# SuperCap.net
KiCad netlist of a schematic drawn in Altium Designer
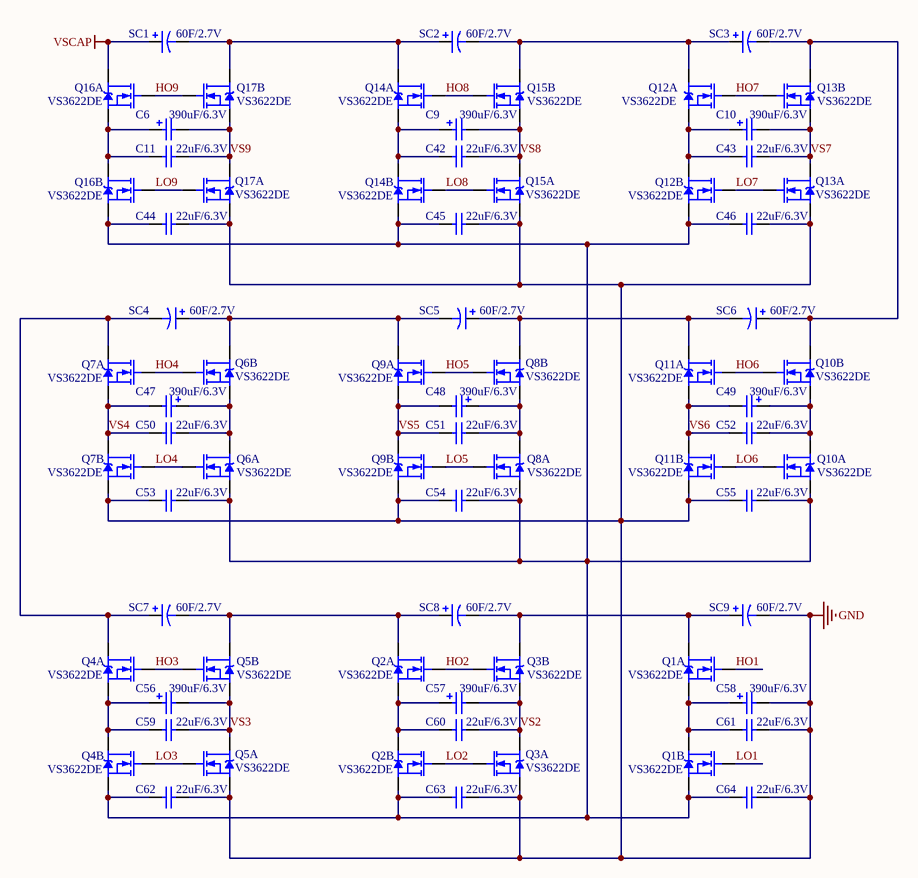
[diagram p0: SuperCap.SchDoc]

(export (version "E")
  (design (tool "Eeschema 10.0.6"))
  (components
    (comp (ref "C6")
      (value "390uF/6.3V")
      (footprint "CS 8*12 - B")
      (description "Polarized Capacitor (Axial)")
      (fields (field (name "PUBLISHER") "Altium Limited"))
      (libsource (lib "Miscellaneous Devices") (part "Cap Pol2"))
    )
    (comp (ref "C9")
      (value "390uF/6.3V")
      (footprint "CS 8*12 - B")
      (description "Polarized Capacitor (Axial)")
      (fields (field (name "PUBLISHER") "Altium Limited"))
      (libsource (lib "Miscellaneous Devices") (part "Cap Pol2"))
    )
    (comp (ref "C10")
      (value "390uF/6.3V")
      (footprint "CS 8*12 - B")
      (description "Polarized Capacitor (Axial)")
      (fields (field (name "PUBLISHER") "Altium Limited"))
      (libsource (lib "Miscellaneous Devices") (part "Cap Pol2"))
    )
    (comp (ref "C11")
      (value "22uF/6.3V")
      (footprint "C0603_M")
      (description "Capacitor")
      (fields (field (name "PUBLISHER") "Altium Limited"))
      (libsource (lib "Miscellaneous Devices") (part "Cap"))
    )
    (comp (ref "C42")
      (value "22uF/6.3V")
      (footprint "C0603_M")
      (description "Capacitor")
      (fields (field (name "PUBLISHER") "Altium Limited"))
      (libsource (lib "Miscellaneous Devices") (part "Cap"))
    )
    (comp (ref "C43")
      (value "22uF/6.3V")
      (footprint "C0603_M")
      (description "Capacitor")
      (fields (field (name "PUBLISHER") "Altium Limited"))
      (libsource (lib "Miscellaneous Devices") (part "Cap"))
    )
    (comp (ref "C44")
      (value "22uF/6.3V")
      (footprint "C0603_M")
      (description "Capacitor")
      (fields (field (name "PUBLISHER") "Altium Limited"))
      (libsource (lib "Miscellaneous Devices") (part "Cap"))
    )
    (comp (ref "C45")
      (value "22uF/6.3V")
      (footprint "C0603_M")
      (description "Capacitor")
      (fields (field (name "PUBLISHER") "Altium Limited"))
      (libsource (lib "Miscellaneous Devices") (part "Cap"))
    )
    (comp (ref "C46")
      (value "22uF/6.3V")
      (footprint "C0603_M")
      (description "Capacitor")
      (fields (field (name "PUBLISHER") "Altium Limited"))
      (libsource (lib "Miscellaneous Devices") (part "Cap"))
    )
    (comp (ref "C47")
      (value "390uF/6.3V")
      (footprint "CS 8*12 - B")
      (description "Polarized Capacitor (Axial)")
      (fields (field (name "PUBLISHER") "Altium Limited"))
      (libsource (lib "Miscellaneous Devices") (part "Cap Pol2"))
    )
    (comp (ref "C48")
      (value "390uF/6.3V")
      (footprint "CS 8*12 - B")
      (description "Polarized Capacitor (Axial)")
      (fields (field (name "PUBLISHER") "Altium Limited"))
      (libsource (lib "Miscellaneous Devices") (part "Cap Pol2"))
    )
    (comp (ref "C49")
      (value "390uF/6.3V")
      (footprint "CS 8*12 - B")
      (description "Polarized Capacitor (Axial)")
      (fields (field (name "PUBLISHER") "Altium Limited"))
      (libsource (lib "Miscellaneous Devices") (part "Cap Pol2"))
    )
    (comp (ref "C50")
      (value "22uF/6.3V")
      (footprint "C0603_M")
      (description "Capacitor")
      (fields (field (name "PUBLISHER") "Altium Limited"))
      (libsource (lib "Miscellaneous Devices") (part "Cap"))
    )
    (comp (ref "C51")
      (value "22uF/6.3V")
      (footprint "C0603_M")
      (description "Capacitor")
      (fields (field (name "PUBLISHER") "Altium Limited"))
      (libsource (lib "Miscellaneous Devices") (part "Cap"))
    )
    (comp (ref "C52")
      (value "22uF/6.3V")
      (footprint "C0603_M")
      (description "Capacitor")
      (fields (field (name "PUBLISHER") "Altium Limited"))
      (libsource (lib "Miscellaneous Devices") (part "Cap"))
    )
    (comp (ref "C53")
      (value "22uF/6.3V")
      (footprint "C0603_M")
      (description "Capacitor")
      (fields (field (name "PUBLISHER") "Altium Limited"))
      (libsource (lib "Miscellaneous Devices") (part "Cap"))
    )
    (comp (ref "C54")
      (value "22uF/6.3V")
      (footprint "C0603_M")
      (description "Capacitor")
      (fields (field (name "PUBLISHER") "Altium Limited"))
      (libsource (lib "Miscellaneous Devices") (part "Cap"))
    )
    (comp (ref "C55")
      (value "22uF/6.3V")
      (footprint "C0603_M")
      (description "Capacitor")
      (fields (field (name "PUBLISHER") "Altium Limited"))
      (libsource (lib "Miscellaneous Devices") (part "Cap"))
    )
    (comp (ref "C56")
      (value "390uF/6.3V")
      (footprint "CS 8*12 - B")
      (description "Polarized Capacitor (Axial)")
      (fields (field (name "PUBLISHER") "Altium Limited"))
      (libsource (lib "Miscellaneous Devices") (part "Cap Pol2"))
    )
    (comp (ref "C57")
      (value "390uF/6.3V")
      (footprint "CS 8*12 - B")
      (description "Polarized Capacitor (Axial)")
      (fields (field (name "PUBLISHER") "Altium Limited"))
      (libsource (lib "Miscellaneous Devices") (part "Cap Pol2"))
    )
    (comp (ref "C58")
      (value "390uF/6.3V")
      (footprint "CS 8*12 - B")
      (description "Polarized Capacitor (Axial)")
      (fields (field (name "PUBLISHER") "Altium Limited"))
      (libsource (lib "Miscellaneous Devices") (part "Cap Pol2"))
    )
    (comp (ref "C59")
      (value "22uF/6.3V")
      (footprint "C0603_M")
      (description "Capacitor")
      (fields (field (name "PUBLISHER") "Altium Limited"))
      (libsource (lib "Miscellaneous Devices") (part "Cap"))
    )
    (comp (ref "C60")
      (value "22uF/6.3V")
      (footprint "C0603_M")
      (description "Capacitor")
      (fields (field (name "PUBLISHER") "Altium Limited"))
      (libsource (lib "Miscellaneous Devices") (part "Cap"))
    )
    (comp (ref "C61")
      (value "22uF/6.3V")
      (footprint "C0603_M")
      (description "Capacitor")
      (fields (field (name "PUBLISHER") "Altium Limited"))
      (libsource (lib "Miscellaneous Devices") (part "Cap"))
    )
    (comp (ref "C62")
      (value "22uF/6.3V")
      (footprint "C0603_M")
      (description "Capacitor")
      (fields (field (name "PUBLISHER") "Altium Limited"))
      (libsource (lib "Miscellaneous Devices") (part "Cap"))
    )
    (comp (ref "C63")
      (value "22uF/6.3V")
      (footprint "C0603_M")
      (description "Capacitor")
      (fields (field (name "PUBLISHER") "Altium Limited"))
      (libsource (lib "Miscellaneous Devices") (part "Cap"))
    )
    (comp (ref "C64")
      (value "22uF/6.3V")
      (footprint "C0603_M")
      (description "Capacitor")
      (libsource (lib "Miscellaneous Devices") (part "Cap"))
    )
    (comp (ref "Q1")
      (value "VS3622DE")
      (footprint "PDFN3333-8_VS3622DE")
      (libsource (lib "my_library") (part "VS3622DE"))
    )
    (comp (ref "Q2")
      (value "VS3622DE")
      (footprint "PDFN3333-8_VS3622DE")
      (libsource (lib "my_library") (part "VS3622DE"))
    )
    (comp (ref "Q3")
      (value "VS3622DE")
      (footprint "PDFN3333-8_VS3622DE")
      (libsource (lib "my_library") (part "VS3622DE"))
    )
    (comp (ref "Q4")
      (value "VS3622DE")
      (footprint "PDFN3333-8_VS3622DE")
      (libsource (lib "my_library") (part "VS3622DE"))
    )
    (comp (ref "Q5")
      (value "VS3622DE")
      (footprint "PDFN3333-8_VS3622DE")
      (libsource (lib "my_library") (part "VS3622DE"))
    )
    (comp (ref "Q6")
      (value "VS3622DE")
      (footprint "PDFN3333-8_VS3622DE")
      (libsource (lib "my_library") (part "VS3622DE"))
    )
    (comp (ref "Q7")
      (value "VS3622DE")
      (footprint "PDFN3333-8_VS3622DE")
      (libsource (lib "my_library") (part "VS3622DE"))
    )
    (comp (ref "Q8")
      (value "VS3622DE")
      (footprint "PDFN3333-8_VS3622DE")
      (libsource (lib "my_library") (part "VS3622DE"))
    )
    (comp (ref "Q9")
      (value "VS3622DE")
      (footprint "PDFN3333-8_VS3622DE")
      (libsource (lib "my_library") (part "VS3622DE"))
    )
    (comp (ref "Q10")
      (value "VS3622DE")
      (footprint "PDFN3333-8_VS3622DE")
      (libsource (lib "my_library") (part "VS3622DE"))
    )
    (comp (ref "Q11")
      (value "VS3622DE")
      (footprint "PDFN3333-8_VS3622DE")
      (libsource (lib "my_library") (part "VS3622DE"))
    )
    (comp (ref "Q12")
      (value "VS3622DE")
      (footprint "PDFN3333-8_VS3622DE")
      (libsource (lib "my_library") (part "VS3622DE"))
    )
    (comp (ref "Q13")
      (value "VS3622DE")
      (footprint "PDFN3333-8_VS3622DE")
      (libsource (lib "my_library") (part "VS3622DE"))
    )
    (comp (ref "Q14")
      (value "VS3622DE")
      (footprint "PDFN3333-8_VS3622DE")
      (libsource (lib "my_library") (part "VS3622DE"))
    )
    (comp (ref "Q15")
      (value "VS3622DE")
      (footprint "PDFN3333-8_VS3622DE")
      (libsource (lib "my_library") (part "VS3622DE"))
    )
    (comp (ref "Q16")
      (value "VS3622DE")
      (footprint "PDFN3333-8_VS3622DE")
      (libsource (lib "my_library") (part "VS3622DE"))
    )
    (comp (ref "Q17")
      (value "VS3622DE")
      (footprint "PDFN3333-8_VS3622DE")
      (libsource (lib "my_library") (part "VS3622DE"))
    )
    (comp (ref "SC1")
      (value "60F/2.7V")
      (footprint "CE-7.5*18*35.5 - BK")
      (description "Polarized Capacitor (Radial)")
      (libsource (lib "Miscellaneous Devices") (part "Cap Pol1"))
    )
    (comp (ref "SC2")
      (value "60F/2.7V")
      (footprint "CE-7.5*18*35.5 - BK")
      (description "Polarized Capacitor (Radial)")
      (libsource (lib "Miscellaneous Devices") (part "Cap Pol1"))
    )
    (comp (ref "SC3")
      (value "60F/2.7V")
      (footprint "CE-7.5*18*35.5 - BK")
      (description "Polarized Capacitor (Radial)")
      (libsource (lib "Miscellaneous Devices") (part "Cap Pol1"))
    )
    (comp (ref "SC4")
      (value "60F/2.7V")
      (footprint "CE-7.5*18*35.5 - BK")
      (description "Polarized Capacitor (Radial)")
      (libsource (lib "") (part "Cap Pol1_1"))
    )
    (comp (ref "SC5")
      (value "60F/2.7V")
      (footprint "CE-7.5*18*35.5 - BK")
      (description "Polarized Capacitor (Radial)")
      (libsource (lib "") (part "Cap Pol1_1"))
    )
    (comp (ref "SC6")
      (value "60F/2.7V")
      (footprint "CE-7.5*18*35.5 - BK")
      (description "Polarized Capacitor (Radial)")
      (libsource (lib "") (part "Cap Pol1_1"))
    )
    (comp (ref "SC7")
      (value "60F/2.7V")
      (footprint "CE-7.5*18*35.5 - BK")
      (description "Polarized Capacitor (Radial)")
      (libsource (lib "Miscellaneous Devices") (part "Cap Pol1"))
    )
    (comp (ref "SC8")
      (value "60F/2.7V")
      (footprint "CE-7.5*18*35.5 - BK")
      (description "Polarized Capacitor (Radial)")
      (libsource (lib "Miscellaneous Devices") (part "Cap Pol1"))
    )
    (comp (ref "SC9")
      (value "60F/2.7V")
      (footprint "CE-7.5*18*35.5 - BK")
      (description "Polarized Capacitor (Radial)")
      (libsource (lib "Miscellaneous Devices") (part "Cap Pol1"))
    )
  )
  (nets
    (net (code "1") (name "/HO1") (class "Default")
      (node (ref "Q1") (pin "G1") (pinfunction "G1_G1") (pintype "passive"))
    )
    (net (code "2") (name "/HO2") (class "Default")
      (node (ref "Q2") (pin "G1") (pinfunction "G1_G1") (pintype "passive"))
      (node (ref "Q3") (pin "G2") (pinfunction "G2_G2") (pintype "passive"))
    )
    (net (code "3") (name "/HO3") (class "Default")
      (node (ref "Q4") (pin "G1") (pinfunction "G1_G1") (pintype "passive"))
      (node (ref "Q5") (pin "G2") (pinfunction "G2_G2") (pintype "passive"))
    )
    (net (code "4") (name "/HO4") (class "Default")
      (node (ref "Q6") (pin "G2") (pinfunction "G2_G2") (pintype "passive"))
      (node (ref "Q7") (pin "G1") (pinfunction "G1_G1") (pintype "passive"))
    )
    (net (code "5") (name "/HO5") (class "Default")
      (node (ref "Q8") (pin "G2") (pinfunction "G2_G2") (pintype "passive"))
      (node (ref "Q9") (pin "G1") (pinfunction "G1_G1") (pintype "passive"))
    )
    (net (code "6") (name "/HO6") (class "Default")
      (node (ref "Q10") (pin "G2") (pinfunction "G2_G2") (pintype "passive"))
      (node (ref "Q11") (pin "G1") (pinfunction "G1_G1") (pintype "passive"))
    )
    (net (code "7") (name "/HO7") (class "Default")
      (node (ref "Q12") (pin "G1") (pinfunction "G1_G1") (pintype "passive"))
      (node (ref "Q13") (pin "G2") (pinfunction "G2_G2") (pintype "passive"))
    )
    (net (code "8") (name "/HO8") (class "Default")
      (node (ref "Q14") (pin "G1") (pinfunction "G1_G1") (pintype "passive"))
      (node (ref "Q15") (pin "G2") (pinfunction "G2_G2") (pintype "passive"))
    )
    (net (code "9") (name "/HO9") (class "Default")
      (node (ref "Q16") (pin "G1") (pinfunction "G1_G1") (pintype "passive"))
      (node (ref "Q17") (pin "G2") (pinfunction "G2_G2") (pintype "passive"))
    )
    (net (code "10") (name "/LO1") (class "Default")
      (node (ref "Q1") (pin "G2") (pinfunction "G2_G2") (pintype "passive"))
    )
    (net (code "11") (name "/LO2") (class "Default")
      (node (ref "Q2") (pin "G2") (pinfunction "G2_G2") (pintype "passive"))
      (node (ref "Q3") (pin "G1") (pinfunction "G1_G1") (pintype "passive"))
    )
    (net (code "12") (name "/LO3") (class "Default")
      (node (ref "Q4") (pin "G2") (pinfunction "G2_G2") (pintype "passive"))
      (node (ref "Q5") (pin "G1") (pinfunction "G1_G1") (pintype "passive"))
    )
    (net (code "13") (name "/LO4") (class "Default")
      (node (ref "Q6") (pin "G1") (pinfunction "G1_G1") (pintype "passive"))
      (node (ref "Q7") (pin "G2") (pinfunction "G2_G2") (pintype "passive"))
    )
    (net (code "14") (name "/LO5") (class "Default")
      (node (ref "Q8") (pin "G1") (pinfunction "G1_G1") (pintype "passive"))
      (node (ref "Q9") (pin "G2") (pinfunction "G2_G2") (pintype "passive"))
    )
    (net (code "15") (name "/LO6") (class "Default")
      (node (ref "Q10") (pin "G1") (pinfunction "G1_G1") (pintype "passive"))
      (node (ref "Q11") (pin "G2") (pinfunction "G2_G2") (pintype "passive"))
    )
    (net (code "16") (name "/LO7") (class "Default")
      (node (ref "Q12") (pin "G2") (pinfunction "G2_G2") (pintype "passive"))
      (node (ref "Q13") (pin "G1") (pinfunction "G1_G1") (pintype "passive"))
    )
    (net (code "17") (name "/LO8") (class "Default")
      (node (ref "Q14") (pin "G2") (pinfunction "G2_G2") (pintype "passive"))
      (node (ref "Q15") (pin "G1") (pinfunction "G1_G1") (pintype "passive"))
    )
    (net (code "18") (name "/LO9") (class "Default")
      (node (ref "Q16") (pin "G2") (pinfunction "G2_G2") (pintype "passive"))
      (node (ref "Q17") (pin "G1") (pinfunction "G1_G1") (pintype "passive"))
    )
    (net (code "19") (name "/VS2") (class "Default")
      (node (ref "C57") (pin "2") (pinfunction "2_2") (pintype "passive"))
      (node (ref "C60") (pin "2") (pinfunction "2_2") (pintype "passive"))
      (node (ref "Q3") (pin "D1") (pinfunction "D1_D1") (pintype "passive"))
      (node (ref "Q3") (pin "S2") (pinfunction "S2_S2") (pintype "passive"))
    )
    (net (code "20") (name "/VS3") (class "Default")
      (node (ref "C56") (pin "2") (pinfunction "2_2") (pintype "passive"))
      (node (ref "C59") (pin "2") (pinfunction "2_2") (pintype "passive"))
      (node (ref "Q5") (pin "D1") (pinfunction "D1_D1") (pintype "passive"))
      (node (ref "Q5") (pin "S2") (pinfunction "S2_S2") (pintype "passive"))
    )
    (net (code "21") (name "/VS4") (class "Default")
      (node (ref "C47") (pin "2") (pinfunction "2_2") (pintype "passive"))
      (node (ref "C50") (pin "1") (pinfunction "1_1") (pintype "passive"))
      (node (ref "Q7") (pin "D2") (pinfunction "D2_D2") (pintype "passive"))
      (node (ref "Q7") (pin "S1") (pinfunction "S1_S1") (pintype "passive"))
    )
    (net (code "22") (name "/VS5") (class "Default")
      (node (ref "C48") (pin "2") (pinfunction "2_2") (pintype "passive"))
      (node (ref "C51") (pin "1") (pinfunction "1_1") (pintype "passive"))
      (node (ref "Q9") (pin "D2") (pinfunction "D2_D2") (pintype "passive"))
      (node (ref "Q9") (pin "S1") (pinfunction "S1_S1") (pintype "passive"))
    )
    (net (code "23") (name "/VS6") (class "Default")
      (node (ref "C49") (pin "2") (pinfunction "2_2") (pintype "passive"))
      (node (ref "C52") (pin "1") (pinfunction "1_1") (pintype "passive"))
      (node (ref "Q11") (pin "D2") (pinfunction "D2_D2") (pintype "passive"))
      (node (ref "Q11") (pin "S1") (pinfunction "S1_S1") (pintype "passive"))
    )
    (net (code "24") (name "/VS7") (class "Default")
      (node (ref "C10") (pin "2") (pinfunction "2_2") (pintype "passive"))
      (node (ref "C43") (pin "2") (pinfunction "2_2") (pintype "passive"))
      (node (ref "Q13") (pin "D1") (pinfunction "D1_D1") (pintype "passive"))
      (node (ref "Q13") (pin "S2") (pinfunction "S2_S2") (pintype "passive"))
    )
    (net (code "25") (name "/VS8") (class "Default")
      (node (ref "C42") (pin "2") (pinfunction "2_2") (pintype "passive"))
      (node (ref "C9") (pin "2") (pinfunction "2_2") (pintype "passive"))
      (node (ref "Q15") (pin "D1") (pinfunction "D1_D1") (pintype "passive"))
      (node (ref "Q15") (pin "S2") (pinfunction "S2_S2") (pintype "passive"))
    )
    (net (code "26") (name "/VS9") (class "Default")
      (node (ref "C11") (pin "2") (pinfunction "2_2") (pintype "passive"))
      (node (ref "C6") (pin "2") (pinfunction "2_2") (pintype "passive"))
      (node (ref "Q17") (pin "D1") (pinfunction "D1_D1") (pintype "passive"))
      (node (ref "Q17") (pin "S2") (pinfunction "S2_S2") (pintype "passive"))
    )
    (net (code "27") (name "GND") (class "Default")
      (node (ref "C44") (pin "2") (pinfunction "2_2") (pintype "passive"))
      (node (ref "C45") (pin "2") (pinfunction "2_2") (pintype "passive"))
      (node (ref "C46") (pin "2") (pinfunction "2_2") (pintype "passive"))
      (node (ref "C53") (pin "1") (pinfunction "1_1") (pintype "passive"))
      (node (ref "C54") (pin "1") (pinfunction "1_1") (pintype "passive"))
      (node (ref "C55") (pin "1") (pinfunction "1_1") (pintype "passive"))
      (node (ref "C58") (pin "2") (pinfunction "2_2") (pintype "passive"))
      (node (ref "C61") (pin "2") (pinfunction "2_2") (pintype "passive"))
      (node (ref "C62") (pin "2") (pinfunction "2_2") (pintype "passive"))
      (node (ref "C63") (pin "2") (pinfunction "2_2") (pintype "passive"))
      (node (ref "C64") (pin "1") (pinfunction "1_1") (pintype "passive"))
      (node (ref "Q11") (pin "S2") (pinfunction "S2_S2") (pintype "passive"))
      (node (ref "Q13") (pin "S1") (pinfunction "S1_S1") (pintype "passive"))
      (node (ref "Q15") (pin "S1") (pinfunction "S1_S1") (pintype "passive"))
      (node (ref "Q17") (pin "S1") (pinfunction "S1_S1") (pintype "passive"))
      (node (ref "Q3") (pin "S1") (pinfunction "S1_S1") (pintype "passive"))
      (node (ref "Q5") (pin "S1") (pinfunction "S1_S1") (pintype "passive"))
      (node (ref "Q7") (pin "S2") (pinfunction "S2_S2") (pintype "passive"))
      (node (ref "Q9") (pin "S2") (pinfunction "S2_S2") (pintype "passive"))
      (node (ref "SC9") (pin "2") (pinfunction "2_2") (pintype "passive"))
    )
    (net (code "28") (name "Net-(C10-Pad1)") (class "Default")
      (node (ref "C10") (pin "1") (pinfunction "1_1") (pintype "passive"))
      (node (ref "C43") (pin "1") (pinfunction "1_1") (pintype "passive"))
      (node (ref "Q12") (pin "D2") (pinfunction "D2_D2") (pintype "passive"))
      (node (ref "Q12") (pin "S1") (pinfunction "S1_S1") (pintype "passive"))
    )
    (net (code "29") (name "Net-(C11-Pad1)") (class "Default")
      (node (ref "C11") (pin "1") (pinfunction "1_1") (pintype "passive"))
      (node (ref "C6") (pin "1") (pinfunction "1_1") (pintype "passive"))
      (node (ref "Q16") (pin "D2") (pinfunction "D2_D2") (pintype "passive"))
      (node (ref "Q16") (pin "S1") (pinfunction "S1_S1") (pintype "passive"))
    )
    (net (code "30") (name "Net-(C42-Pad1)") (class "Default")
      (node (ref "C42") (pin "1") (pinfunction "1_1") (pintype "passive"))
      (node (ref "C9") (pin "1") (pinfunction "1_1") (pintype "passive"))
      (node (ref "Q14") (pin "D2") (pinfunction "D2_D2") (pintype "passive"))
      (node (ref "Q14") (pin "S1") (pinfunction "S1_S1") (pintype "passive"))
    )
    (net (code "31") (name "Net-(C44-Pad1)") (class "Default")
      (node (ref "C44") (pin "1") (pinfunction "1_1") (pintype "passive"))
      (node (ref "C45") (pin "1") (pinfunction "1_1") (pintype "passive"))
      (node (ref "C46") (pin "1") (pinfunction "1_1") (pintype "passive"))
      (node (ref "C53") (pin "2") (pinfunction "2_2") (pintype "passive"))
      (node (ref "C54") (pin "2") (pinfunction "2_2") (pintype "passive"))
      (node (ref "C55") (pin "2") (pinfunction "2_2") (pintype "passive"))
      (node (ref "C62") (pin "1") (pinfunction "1_1") (pintype "passive"))
      (node (ref "C63") (pin "1") (pinfunction "1_1") (pintype "passive"))
      (node (ref "C64") (pin "2") (pinfunction "2_2") (pintype "passive"))
      (node (ref "Q1") (pin "S2") (pinfunction "S2_S2") (pintype "passive"))
      (node (ref "Q10") (pin "S1") (pinfunction "S1_S1") (pintype "passive"))
      (node (ref "Q12") (pin "S2") (pinfunction "S2_S2") (pintype "passive"))
      (node (ref "Q14") (pin "S2") (pinfunction "S2_S2") (pintype "passive"))
      (node (ref "Q16") (pin "S2") (pinfunction "S2_S2") (pintype "passive"))
      (node (ref "Q2") (pin "S2") (pinfunction "S2_S2") (pintype "passive"))
      (node (ref "Q4") (pin "S2") (pinfunction "S2_S2") (pintype "passive"))
      (node (ref "Q6") (pin "S1") (pinfunction "S1_S1") (pintype "passive"))
      (node (ref "Q8") (pin "S1") (pinfunction "S1_S1") (pintype "passive"))
    )
    (net (code "32") (name "Net-(C47-Pad1)") (class "Default")
      (node (ref "C47") (pin "1") (pinfunction "1_1") (pintype "passive"))
      (node (ref "C50") (pin "2") (pinfunction "2_2") (pintype "passive"))
      (node (ref "Q6") (pin "D1") (pinfunction "D1_D1") (pintype "passive"))
      (node (ref "Q6") (pin "S2") (pinfunction "S2_S2") (pintype "passive"))
    )
    (net (code "33") (name "Net-(C48-Pad1)") (class "Default")
      (node (ref "C48") (pin "1") (pinfunction "1_1") (pintype "passive"))
      (node (ref "C51") (pin "2") (pinfunction "2_2") (pintype "passive"))
      (node (ref "Q8") (pin "D1") (pinfunction "D1_D1") (pintype "passive"))
      (node (ref "Q8") (pin "S2") (pinfunction "S2_S2") (pintype "passive"))
    )
    (net (code "34") (name "Net-(C49-Pad1)") (class "Default")
      (node (ref "C49") (pin "1") (pinfunction "1_1") (pintype "passive"))
      (node (ref "C52") (pin "2") (pinfunction "2_2") (pintype "passive"))
      (node (ref "Q10") (pin "D1") (pinfunction "D1_D1") (pintype "passive"))
      (node (ref "Q10") (pin "S2") (pinfunction "S2_S2") (pintype "passive"))
    )
    (net (code "35") (name "Net-(C56-Pad1)") (class "Default")
      (node (ref "C56") (pin "1") (pinfunction "1_1") (pintype "passive"))
      (node (ref "C59") (pin "1") (pinfunction "1_1") (pintype "passive"))
      (node (ref "Q4") (pin "D2") (pinfunction "D2_D2") (pintype "passive"))
      (node (ref "Q4") (pin "S1") (pinfunction "S1_S1") (pintype "passive"))
    )
    (net (code "36") (name "Net-(C57-Pad1)") (class "Default")
      (node (ref "C57") (pin "1") (pinfunction "1_1") (pintype "passive"))
      (node (ref "C60") (pin "1") (pinfunction "1_1") (pintype "passive"))
      (node (ref "Q2") (pin "D2") (pinfunction "D2_D2") (pintype "passive"))
      (node (ref "Q2") (pin "S1") (pinfunction "S1_S1") (pintype "passive"))
    )
    (net (code "37") (name "Net-(C58-Pad1)") (class "Default")
      (node (ref "C58") (pin "1") (pinfunction "1_1") (pintype "passive"))
      (node (ref "C61") (pin "1") (pinfunction "1_1") (pintype "passive"))
      (node (ref "Q1") (pin "D2") (pinfunction "D2_D2") (pintype "passive"))
      (node (ref "Q1") (pin "S1") (pinfunction "S1_S1") (pintype "passive"))
    )
    (net (code "38") (name "Net-(Q1-PadD1)") (class "Default")
      (node (ref "Q1") (pin "D1") (pinfunction "D1_D1") (pintype "passive"))
      (node (ref "Q3") (pin "D2") (pinfunction "D2_D2") (pintype "passive"))
      (node (ref "SC8") (pin "2") (pinfunction "2_2") (pintype "passive"))
      (node (ref "SC9") (pin "1") (pinfunction "1_1") (pintype "passive"))
    )
    (net (code "39") (name "Net-(Q2-PadD1)") (class "Default")
      (node (ref "Q2") (pin "D1") (pinfunction "D1_D1") (pintype "passive"))
      (node (ref "Q5") (pin "D2") (pinfunction "D2_D2") (pintype "passive"))
      (node (ref "SC7") (pin "2") (pinfunction "2_2") (pintype "passive"))
      (node (ref "SC8") (pin "1") (pinfunction "1_1") (pintype "passive"))
    )
    (net (code "40") (name "Net-(Q4-PadD1)") (class "Default")
      (node (ref "Q4") (pin "D1") (pinfunction "D1_D1") (pintype "passive"))
      (node (ref "Q7") (pin "D1") (pinfunction "D1_D1") (pintype "passive"))
      (node (ref "SC4") (pin "2") (pinfunction "2_2") (pintype "passive"))
      (node (ref "SC7") (pin "1") (pinfunction "1_1") (pintype "passive"))
    )
    (net (code "41") (name "Net-(Q6-PadD2)") (class "Default")
      (node (ref "Q6") (pin "D2") (pinfunction "D2_D2") (pintype "passive"))
      (node (ref "Q9") (pin "D1") (pinfunction "D1_D1") (pintype "passive"))
      (node (ref "SC4") (pin "1") (pinfunction "1_1") (pintype "passive"))
      (node (ref "SC5") (pin "2") (pinfunction "2_2") (pintype "passive"))
    )
    (net (code "42") (name "Net-(Q10-PadD2)") (class "Default")
      (node (ref "Q10") (pin "D2") (pinfunction "D2_D2") (pintype "passive"))
      (node (ref "Q13") (pin "D2") (pinfunction "D2_D2") (pintype "passive"))
      (node (ref "SC3") (pin "2") (pinfunction "2_2") (pintype "passive"))
      (node (ref "SC6") (pin "1") (pinfunction "1_1") (pintype "passive"))
    )
    (net (code "43") (name "Net-(Q11-PadD1)") (class "Default")
      (node (ref "Q11") (pin "D1") (pinfunction "D1_D1") (pintype "passive"))
      (node (ref "Q8") (pin "D2") (pinfunction "D2_D2") (pintype "passive"))
      (node (ref "SC5") (pin "1") (pinfunction "1_1") (pintype "passive"))
      (node (ref "SC6") (pin "2") (pinfunction "2_2") (pintype "passive"))
    )
    (net (code "44") (name "Net-(Q12-PadD1)") (class "Default")
      (node (ref "Q12") (pin "D1") (pinfunction "D1_D1") (pintype "passive"))
      (node (ref "Q15") (pin "D2") (pinfunction "D2_D2") (pintype "passive"))
      (node (ref "SC2") (pin "2") (pinfunction "2_2") (pintype "passive"))
      (node (ref "SC3") (pin "1") (pinfunction "1_1") (pintype "passive"))
    )
    (net (code "45") (name "Net-(Q14-PadD1)") (class "Default")
      (node (ref "Q14") (pin "D1") (pinfunction "D1_D1") (pintype "passive"))
      (node (ref "Q17") (pin "D2") (pinfunction "D2_D2") (pintype "passive"))
      (node (ref "SC1") (pin "2") (pinfunction "2_2") (pintype "passive"))
      (node (ref "SC2") (pin "1") (pinfunction "1_1") (pintype "passive"))
    )
    (net (code "46") (name "VSCAP") (class "Default")
      (node (ref "Q16") (pin "D1") (pinfunction "D1_D1") (pintype "passive"))
      (node (ref "SC1") (pin "1") (pinfunction "1_1") (pintype "passive"))
    )
  )
)
